# relay.net
KiCad netlist of a schematic drawn in Altium Designer
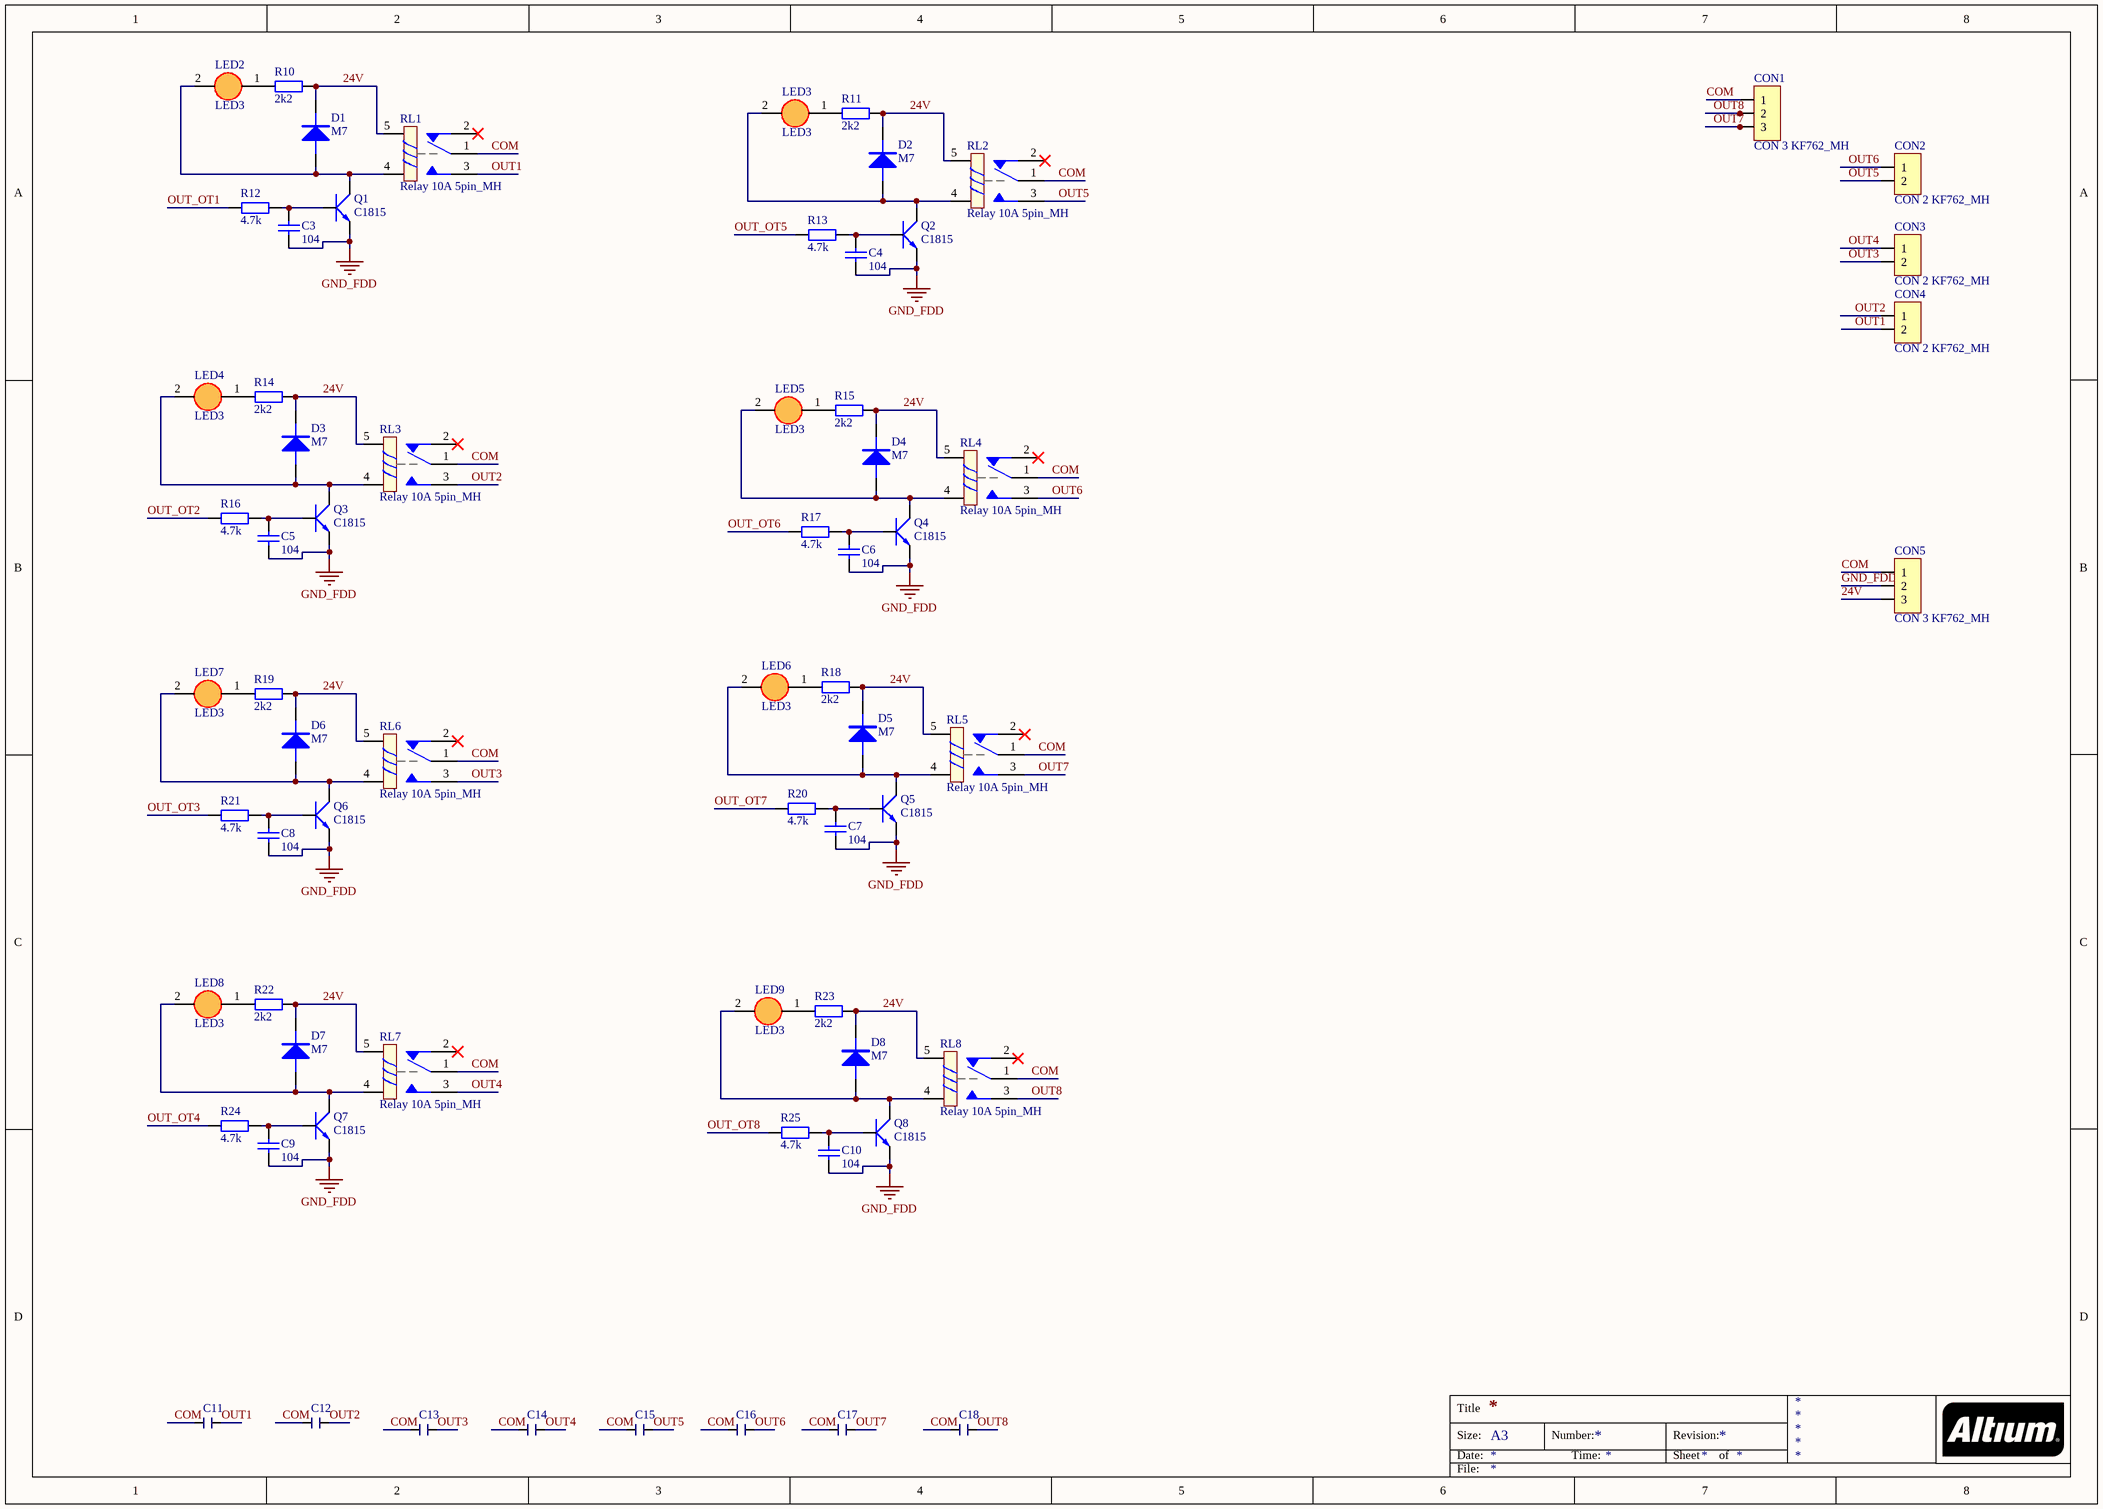
[diagram p0: relay.SchDoc]

(export (version "E")
  (design (tool "Eeschema 10.0.6"))
  (components
    (comp (ref "C3")
      (value "104")
      (footprint "TU_SMD_0805")
      (libsource (lib "MH_DA_THU_VIEN_ALTIUM_19112016") (part "TU_SMD_0805_MH"))
    )
    (comp (ref "C4")
      (value "104")
      (footprint "TU_SMD_0805")
      (libsource (lib "MH_DA_THU_VIEN_ALTIUM_19112016") (part "TU_SMD_0805_MH"))
    )
    (comp (ref "C5")
      (value "104")
      (footprint "TU_SMD_0805")
      (libsource (lib "MH_DA_THU_VIEN_ALTIUM_19112016") (part "TU_SMD_0805_MH"))
    )
    (comp (ref "C6")
      (value "104")
      (footprint "TU_SMD_0805")
      (libsource (lib "MH_DA_THU_VIEN_ALTIUM_19112016") (part "TU_SMD_0805_MH"))
    )
    (comp (ref "C7")
      (value "104")
      (footprint "TU_SMD_0805")
      (libsource (lib "MH_DA_THU_VIEN_ALTIUM_19112016") (part "TU_SMD_0805_MH"))
    )
    (comp (ref "C8")
      (value "104")
      (footprint "TU_SMD_0805")
      (libsource (lib "MH_DA_THU_VIEN_ALTIUM_19112016") (part "TU_SMD_0805_MH"))
    )
    (comp (ref "C9")
      (value "104")
      (footprint "TU_SMD_0805")
      (libsource (lib "MH_DA_THU_VIEN_ALTIUM_19112016") (part "TU_SMD_0805_MH"))
    )
    (comp (ref "C10")
      (value "104")
      (footprint "TU_SMD_0805")
      (libsource (lib "MH_DA_THU_VIEN_ALTIUM_19112016") (part "TU_SMD_0805_MH"))
    )
    (comp (ref "C11")
      (value "TU_CAO__AP_103_102_101_1KV_MH")
      (footprint "TU_TATA_5.08")
      (description "103 1KV")
      (libsource (lib "MH_DA_THU_VIEN_ALTIUM_19112016") (part "TU_CAO__AP_103_102_101_1KV_MH"))
    )
    (comp (ref "C12")
      (value "TU_CAO__AP_103_102_101_1KV_MH")
      (footprint "TU_TATA_5.08")
      (description "103 1KV")
      (libsource (lib "MH_DA_THU_VIEN_ALTIUM_19112016") (part "TU_CAO__AP_103_102_101_1KV_MH"))
    )
    (comp (ref "C13")
      (value "TU_CAO__AP_103_102_101_1KV_MH")
      (footprint "TU_TATA_5.08")
      (description "103 1KV")
      (libsource (lib "MH_DA_THU_VIEN_ALTIUM_19112016") (part "TU_CAO__AP_103_102_101_1KV_MH"))
    )
    (comp (ref "C14")
      (value "TU_CAO__AP_103_102_101_1KV_MH")
      (footprint "TU_TATA_5.08")
      (description "103 1KV")
      (libsource (lib "MH_DA_THU_VIEN_ALTIUM_19112016") (part "TU_CAO__AP_103_102_101_1KV_MH"))
    )
    (comp (ref "C15")
      (value "TU_CAO__AP_103_102_101_1KV_MH")
      (footprint "TU_TATA_5.08")
      (description "103 1KV")
      (libsource (lib "MH_DA_THU_VIEN_ALTIUM_19112016") (part "TU_CAO__AP_103_102_101_1KV_MH"))
    )
    (comp (ref "C16")
      (value "TU_CAO__AP_103_102_101_1KV_MH")
      (footprint "TU_TATA_5.08")
      (description "103 1KV")
      (libsource (lib "MH_DA_THU_VIEN_ALTIUM_19112016") (part "TU_CAO__AP_103_102_101_1KV_MH"))
    )
    (comp (ref "C17")
      (value "TU_CAO__AP_103_102_101_1KV_MH")
      (footprint "TU_TATA_5.08")
      (description "103 1KV")
      (libsource (lib "MH_DA_THU_VIEN_ALTIUM_19112016") (part "TU_CAO__AP_103_102_101_1KV_MH"))
    )
    (comp (ref "C18")
      (value "TU_CAO__AP_103_102_101_1KV_MH")
      (footprint "TU_TATA_5.08")
      (description "103 1KV")
      (libsource (lib "MH_DA_THU_VIEN_ALTIUM_19112016") (part "TU_CAO__AP_103_102_101_1KV_MH"))
    )
    (comp (ref "CON1")
      (value "CON 3 KF762_MH")
      (footprint "Con 3 KF762")
      (description "CON 3 KF762 - 3P 7.62mm")
      (libsource (lib "MH_DA_THU_VIEN_ALTIUM_19112016") (part "CON 3 KF762_MH"))
    )
    (comp (ref "CON2")
      (value "CON 2 KF762_MH")
      (footprint "Con 2 KF762")
      (description "CON 2 KF762 - 2P 7.62mm")
      (libsource (lib "MH_DA_THU_VIEN_ALTIUM_19112016") (part "CON 2 KF762_MH"))
    )
    (comp (ref "CON3")
      (value "CON 2 KF762_MH")
      (footprint "Con 2 KF762")
      (description "CON 2 KF762 - 2P 7.62mm")
      (libsource (lib "MH_DA_THU_VIEN_ALTIUM_19112016") (part "CON 2 KF762_MH"))
    )
    (comp (ref "CON4")
      (value "CON 2 KF762_MH")
      (footprint "Con 2 KF762")
      (description "CON 2 KF762 - 2P 7.62mm")
      (libsource (lib "MH_DA_THU_VIEN_ALTIUM_19112016") (part "CON 2 KF762_MH"))
    )
    (comp (ref "CON5")
      (value "CON 3 KF762_MH")
      (footprint "Con 3 KF762")
      (description "CON 3 KF762 - 3P 7.62mm")
      (libsource (lib "MH_DA_THU_VIEN_ALTIUM_19112016") (part "CON 3 KF762_MH"))
    )
    (comp (ref "D1")
      (value "M7")
      (footprint "SOD80")
      (description "Diode 1N4148 SOD80 450mA 100V ( LL34 1N4148 SMD)")
      (libsource (lib "MH_DA_THU_VIEN_ALTIUM_19112016") (part "Diode 1N4148 SOD80 450mA 100V ( LL34 1N4148 SMD)_MH"))
    )
    (comp (ref "D2")
      (value "M7")
      (footprint "SOD80")
      (description "Diode 1N4148 SOD80 450mA 100V ( LL34 1N4148 SMD)")
      (libsource (lib "MH_DA_THU_VIEN_ALTIUM_19112016") (part "Diode 1N4148 SOD80 450mA 100V ( LL34 1N4148 SMD)_MH"))
    )
    (comp (ref "D3")
      (value "M7")
      (footprint "SOD80")
      (description "Diode 1N4148 SOD80 450mA 100V ( LL34 1N4148 SMD)")
      (libsource (lib "MH_DA_THU_VIEN_ALTIUM_19112016") (part "Diode 1N4148 SOD80 450mA 100V ( LL34 1N4148 SMD)_MH"))
    )
    (comp (ref "D4")
      (value "M7")
      (footprint "SOD80")
      (description "Diode 1N4148 SOD80 450mA 100V ( LL34 1N4148 SMD)")
      (libsource (lib "MH_DA_THU_VIEN_ALTIUM_19112016") (part "Diode 1N4148 SOD80 450mA 100V ( LL34 1N4148 SMD)_MH"))
    )
    (comp (ref "D5")
      (value "M7")
      (footprint "SOD80")
      (description "Diode 1N4148 SOD80 450mA 100V ( LL34 1N4148 SMD)")
      (libsource (lib "MH_DA_THU_VIEN_ALTIUM_19112016") (part "Diode 1N4148 SOD80 450mA 100V ( LL34 1N4148 SMD)_MH"))
    )
    (comp (ref "D6")
      (value "M7")
      (footprint "SOD80")
      (description "Diode 1N4148 SOD80 450mA 100V ( LL34 1N4148 SMD)")
      (libsource (lib "MH_DA_THU_VIEN_ALTIUM_19112016") (part "Diode 1N4148 SOD80 450mA 100V ( LL34 1N4148 SMD)_MH"))
    )
    (comp (ref "D7")
      (value "M7")
      (footprint "SOD80")
      (description "Diode 1N4148 SOD80 450mA 100V ( LL34 1N4148 SMD)")
      (libsource (lib "MH_DA_THU_VIEN_ALTIUM_19112016") (part "Diode 1N4148 SOD80 450mA 100V ( LL34 1N4148 SMD)_MH"))
    )
    (comp (ref "D8")
      (value "M7")
      (footprint "SOD80")
      (description "Diode 1N4148 SOD80 450mA 100V ( LL34 1N4148 SMD)")
      (libsource (lib "MH_DA_THU_VIEN_ALTIUM_19112016") (part "Diode 1N4148 SOD80 450mA 100V ( LL34 1N4148 SMD)_MH"))
    )
    (comp (ref "LED2")
      (value "LED3")
      (footprint "LED 3mm Do")
      (description "LED 3mm")
      (libsource (lib "MH_DA_THU_VIEN_ALTIUM_19112016") (part "LED 3mm_MH"))
    )
    (comp (ref "LED3")
      (value "LED3")
      (footprint "LED 3mm Do")
      (description "LED 3mm")
      (libsource (lib "MH_DA_THU_VIEN_ALTIUM_19112016") (part "LED 3mm_MH"))
    )
    (comp (ref "LED4")
      (value "LED3")
      (footprint "LED 3mm Do")
      (description "LED 3mm")
      (libsource (lib "MH_DA_THU_VIEN_ALTIUM_19112016") (part "LED 3mm_MH"))
    )
    (comp (ref "LED5")
      (value "LED3")
      (footprint "LED 3mm Do")
      (description "LED 3mm")
      (libsource (lib "MH_DA_THU_VIEN_ALTIUM_19112016") (part "LED 3mm_MH"))
    )
    (comp (ref "LED6")
      (value "LED3")
      (footprint "LED 3mm Do")
      (description "LED 3mm")
      (libsource (lib "MH_DA_THU_VIEN_ALTIUM_19112016") (part "LED 3mm_MH"))
    )
    (comp (ref "LED7")
      (value "LED3")
      (footprint "LED 3mm Do")
      (description "LED 3mm")
      (libsource (lib "MH_DA_THU_VIEN_ALTIUM_19112016") (part "LED 3mm_MH"))
    )
    (comp (ref "LED8")
      (value "LED3")
      (footprint "LED 3mm Do")
      (description "LED 3mm")
      (libsource (lib "MH_DA_THU_VIEN_ALTIUM_19112016") (part "LED 3mm_MH"))
    )
    (comp (ref "LED9")
      (value "LED3")
      (footprint "LED 3mm Do")
      (description "LED 3mm")
      (libsource (lib "MH_DA_THU_VIEN_ALTIUM_19112016") (part "LED 3mm_MH"))
    )
    (comp (ref "Q1")
      (value "C1815")
      (footprint "SOT23")
      (libsource (lib "MH_DA_THU_VIEN_ALTIUM_19112016") (part "C1815 SOT23 TRANS NPN 0.15A 50V (SMD-HF)_MH"))
    )
    (comp (ref "Q2")
      (value "C1815")
      (footprint "SOT23")
      (libsource (lib "MH_DA_THU_VIEN_ALTIUM_19112016") (part "C1815 SOT23 TRANS NPN 0.15A 50V (SMD-HF)_MH"))
    )
    (comp (ref "Q3")
      (value "C1815")
      (footprint "SOT23")
      (libsource (lib "MH_DA_THU_VIEN_ALTIUM_19112016") (part "C1815 SOT23 TRANS NPN 0.15A 50V (SMD-HF)_MH"))
    )
    (comp (ref "Q4")
      (value "C1815")
      (footprint "SOT23")
      (libsource (lib "MH_DA_THU_VIEN_ALTIUM_19112016") (part "C1815 SOT23 TRANS NPN 0.15A 50V (SMD-HF)_MH"))
    )
    (comp (ref "Q5")
      (value "C1815")
      (footprint "SOT23")
      (libsource (lib "MH_DA_THU_VIEN_ALTIUM_19112016") (part "C1815 SOT23 TRANS NPN 0.15A 50V (SMD-HF)_MH"))
    )
    (comp (ref "Q6")
      (value "C1815")
      (footprint "SOT23")
      (libsource (lib "MH_DA_THU_VIEN_ALTIUM_19112016") (part "C1815 SOT23 TRANS NPN 0.15A 50V (SMD-HF)_MH"))
    )
    (comp (ref "Q7")
      (value "C1815")
      (footprint "SOT23")
      (libsource (lib "MH_DA_THU_VIEN_ALTIUM_19112016") (part "C1815 SOT23 TRANS NPN 0.15A 50V (SMD-HF)_MH"))
    )
    (comp (ref "Q8")
      (value "C1815")
      (footprint "SOT23")
      (libsource (lib "MH_DA_THU_VIEN_ALTIUM_19112016") (part "C1815 SOT23 TRANS NPN 0.15A 50V (SMD-HF)_MH"))
    )
    (comp (ref "R10")
      (value "2k2")
      (footprint "Tro SMD 0805")
      (description "TRO_SMD_0805")
      (libsource (lib "MH_DA_THU_VIEN_ALTIUM_19112016") (part "TRO_SMD_0805_MH"))
    )
    (comp (ref "R11")
      (value "2k2")
      (footprint "Tro SMD 0805")
      (description "TRO_SMD_0805")
      (libsource (lib "MH_DA_THU_VIEN_ALTIUM_19112016") (part "TRO_SMD_0805_MH"))
    )
    (comp (ref "R12")
      (value "4.7k")
      (footprint "Tro SMD 0805")
      (description "TRO_SMD_0805")
      (libsource (lib "MH_DA_THU_VIEN_ALTIUM_19112016") (part "TRO_SMD_0805_MH"))
    )
    (comp (ref "R13")
      (value "4.7k")
      (footprint "Tro SMD 0805")
      (description "TRO_SMD_0805")
      (libsource (lib "MH_DA_THU_VIEN_ALTIUM_19112016") (part "TRO_SMD_0805_MH"))
    )
    (comp (ref "R14")
      (value "2k2")
      (footprint "Tro SMD 0805")
      (description "TRO_SMD_0805")
      (libsource (lib "MH_DA_THU_VIEN_ALTIUM_19112016") (part "TRO_SMD_0805_MH"))
    )
    (comp (ref "R15")
      (value "2k2")
      (footprint "Tro SMD 0805")
      (description "TRO_SMD_0805")
      (libsource (lib "MH_DA_THU_VIEN_ALTIUM_19112016") (part "TRO_SMD_0805_MH"))
    )
    (comp (ref "R16")
      (value "4.7k")
      (footprint "Tro SMD 0805")
      (description "TRO_SMD_0805")
      (libsource (lib "MH_DA_THU_VIEN_ALTIUM_19112016") (part "TRO_SMD_0805_MH"))
    )
    (comp (ref "R17")
      (value "4.7k")
      (footprint "Tro SMD 0805")
      (description "TRO_SMD_0805")
      (libsource (lib "MH_DA_THU_VIEN_ALTIUM_19112016") (part "TRO_SMD_0805_MH"))
    )
    (comp (ref "R18")
      (value "2k2")
      (footprint "Tro SMD 0805")
      (description "TRO_SMD_0805")
      (libsource (lib "MH_DA_THU_VIEN_ALTIUM_19112016") (part "TRO_SMD_0805_MH"))
    )
    (comp (ref "R19")
      (value "2k2")
      (footprint "Tro SMD 0805")
      (description "TRO_SMD_0805")
      (libsource (lib "MH_DA_THU_VIEN_ALTIUM_19112016") (part "TRO_SMD_0805_MH"))
    )
    (comp (ref "R20")
      (value "4.7k")
      (footprint "Tro SMD 0805")
      (description "TRO_SMD_0805")
      (libsource (lib "MH_DA_THU_VIEN_ALTIUM_19112016") (part "TRO_SMD_0805_MH"))
    )
    (comp (ref "R21")
      (value "4.7k")
      (footprint "Tro SMD 0805")
      (description "TRO_SMD_0805")
      (libsource (lib "MH_DA_THU_VIEN_ALTIUM_19112016") (part "TRO_SMD_0805_MH"))
    )
    (comp (ref "R22")
      (value "2k2")
      (footprint "Tro SMD 0805")
      (description "TRO_SMD_0805")
      (libsource (lib "MH_DA_THU_VIEN_ALTIUM_19112016") (part "TRO_SMD_0805_MH"))
    )
    (comp (ref "R23")
      (value "2k2")
      (footprint "Tro SMD 0805")
      (description "TRO_SMD_0805")
      (libsource (lib "MH_DA_THU_VIEN_ALTIUM_19112016") (part "TRO_SMD_0805_MH"))
    )
    (comp (ref "R24")
      (value "4.7k")
      (footprint "Tro SMD 0805")
      (description "TRO_SMD_0805")
      (libsource (lib "MH_DA_THU_VIEN_ALTIUM_19112016") (part "TRO_SMD_0805_MH"))
    )
    (comp (ref "R25")
      (value "4.7k")
      (footprint "Tro SMD 0805")
      (description "TRO_SMD_0805")
      (libsource (lib "MH_DA_THU_VIEN_ALTIUM_19112016") (part "TRO_SMD_0805_MH"))
    )
    (comp (ref "RL1")
      (value "Relay 10A 5pin_MH")
      (footprint "relay 10A 5pin")
      (description "Relay")
      (libsource (lib "MH_DA_THU_VIEN_ALTIUM_19112016") (part "Relay 10A 5pin_MH"))
    )
    (comp (ref "RL2")
      (value "Relay 10A 5pin_MH")
      (footprint "relay 10A 5pin")
      (description "Relay")
      (libsource (lib "MH_DA_THU_VIEN_ALTIUM_19112016") (part "Relay 10A 5pin_MH"))
    )
    (comp (ref "RL3")
      (value "Relay 10A 5pin_MH")
      (footprint "relay 10A 5pin")
      (description "Relay")
      (libsource (lib "MH_DA_THU_VIEN_ALTIUM_19112016") (part "Relay 10A 5pin_MH"))
    )
    (comp (ref "RL4")
      (value "Relay 10A 5pin_MH")
      (footprint "relay 10A 5pin")
      (description "Relay")
      (libsource (lib "MH_DA_THU_VIEN_ALTIUM_19112016") (part "Relay 10A 5pin_MH"))
    )
    (comp (ref "RL5")
      (value "Relay 10A 5pin_MH")
      (footprint "relay 10A 5pin")
      (description "Relay")
      (libsource (lib "MH_DA_THU_VIEN_ALTIUM_19112016") (part "Relay 10A 5pin_MH"))
    )
    (comp (ref "RL6")
      (value "Relay 10A 5pin_MH")
      (footprint "relay 10A 5pin")
      (description "Relay")
      (libsource (lib "MH_DA_THU_VIEN_ALTIUM_19112016") (part "Relay 10A 5pin_MH"))
    )
    (comp (ref "RL7")
      (value "Relay 10A 5pin_MH")
      (footprint "relay 10A 5pin")
      (description "Relay")
      (libsource (lib "MH_DA_THU_VIEN_ALTIUM_19112016") (part "Relay 10A 5pin_MH"))
    )
    (comp (ref "RL8")
      (value "Relay 10A 5pin_MH")
      (footprint "relay 10A 5pin")
      (description "Relay")
      (libsource (lib "MH_DA_THU_VIEN_ALTIUM_19112016") (part "Relay 10A 5pin_MH"))
    )
  )
  (nets
    (net (code "1") (name "/24V") (class "Default")
      (node (ref "CON5") (pin "3") (pinfunction "3_3") (pintype "passive"))
      (node (ref "D1") (pin "2") (pinfunction "2_2") (pintype "passive"))
      (node (ref "D2") (pin "2") (pinfunction "2_2") (pintype "passive"))
      (node (ref "D3") (pin "2") (pinfunction "2_2") (pintype "passive"))
      (node (ref "D4") (pin "2") (pinfunction "2_2") (pintype "passive"))
      (node (ref "D5") (pin "2") (pinfunction "2_2") (pintype "passive"))
      (node (ref "D6") (pin "2") (pinfunction "2_2") (pintype "passive"))
      (node (ref "D7") (pin "2") (pinfunction "2_2") (pintype "passive"))
      (node (ref "D8") (pin "2") (pinfunction "2_2") (pintype "passive"))
      (node (ref "R10") (pin "2") (pinfunction "2_2") (pintype "passive"))
      (node (ref "R11") (pin "2") (pinfunction "2_2") (pintype "passive"))
      (node (ref "R14") (pin "2") (pinfunction "2_2") (pintype "passive"))
      (node (ref "R15") (pin "2") (pinfunction "2_2") (pintype "passive"))
      (node (ref "R18") (pin "2") (pinfunction "2_2") (pintype "passive"))
      (node (ref "R19") (pin "2") (pinfunction "2_2") (pintype "passive"))
      (node (ref "R22") (pin "2") (pinfunction "2_2") (pintype "passive"))
      (node (ref "R23") (pin "2") (pinfunction "2_2") (pintype "passive"))
      (node (ref "RL1") (pin "5") (pinfunction "5_5") (pintype "passive"))
      (node (ref "RL2") (pin "5") (pinfunction "5_5") (pintype "passive"))
      (node (ref "RL3") (pin "5") (pinfunction "5_5") (pintype "passive"))
      (node (ref "RL4") (pin "5") (pinfunction "5_5") (pintype "passive"))
      (node (ref "RL5") (pin "5") (pinfunction "5_5") (pintype "passive"))
      (node (ref "RL6") (pin "5") (pinfunction "5_5") (pintype "passive"))
      (node (ref "RL7") (pin "5") (pinfunction "5_5") (pintype "passive"))
      (node (ref "RL8") (pin "5") (pinfunction "5_5") (pintype "passive"))
    )
    (net (code "2") (name "/COM") (class "Default")
      (node (ref "C11") (pin "1") (pinfunction "1_1") (pintype "passive"))
      (node (ref "C12") (pin "1") (pinfunction "1_1") (pintype "passive"))
      (node (ref "C13") (pin "1") (pinfunction "1_1") (pintype "passive"))
      (node (ref "C14") (pin "1") (pinfunction "1_1") (pintype "passive"))
      (node (ref "C15") (pin "1") (pinfunction "1_1") (pintype "passive"))
      (node (ref "C16") (pin "1") (pinfunction "1_1") (pintype "passive"))
      (node (ref "C17") (pin "1") (pinfunction "1_1") (pintype "passive"))
      (node (ref "C18") (pin "1") (pinfunction "1_1") (pintype "passive"))
      (node (ref "CON1") (pin "1") (pinfunction "1_1") (pintype "passive"))
      (node (ref "CON5") (pin "1") (pinfunction "1_1") (pintype "passive"))
      (node (ref "RL1") (pin "1") (pinfunction "1_1") (pintype "passive"))
      (node (ref "RL2") (pin "1") (pinfunction "1_1") (pintype "passive"))
      (node (ref "RL3") (pin "1") (pinfunction "1_1") (pintype "passive"))
      (node (ref "RL4") (pin "1") (pinfunction "1_1") (pintype "passive"))
      (node (ref "RL5") (pin "1") (pinfunction "1_1") (pintype "passive"))
      (node (ref "RL6") (pin "1") (pinfunction "1_1") (pintype "passive"))
      (node (ref "RL7") (pin "1") (pinfunction "1_1") (pintype "passive"))
      (node (ref "RL8") (pin "1") (pinfunction "1_1") (pintype "passive"))
    )
    (net (code "3") (name "/OUT1") (class "Default")
      (node (ref "C11") (pin "2") (pinfunction "2_2") (pintype "passive"))
      (node (ref "CON4") (pin "2") (pinfunction "2_2") (pintype "passive"))
      (node (ref "RL1") (pin "3") (pinfunction "3_3") (pintype "passive"))
    )
    (net (code "4") (name "/OUT2") (class "Default")
      (node (ref "C12") (pin "2") (pinfunction "2_2") (pintype "passive"))
      (node (ref "CON4") (pin "1") (pinfunction "1_1") (pintype "passive"))
      (node (ref "RL3") (pin "3") (pinfunction "3_3") (pintype "passive"))
    )
    (net (code "5") (name "/OUT3") (class "Default")
      (node (ref "C13") (pin "2") (pinfunction "2_2") (pintype "passive"))
      (node (ref "CON3") (pin "2") (pinfunction "2_2") (pintype "passive"))
      (node (ref "RL6") (pin "3") (pinfunction "3_3") (pintype "passive"))
    )
    (net (code "6") (name "/OUT4") (class "Default")
      (node (ref "C14") (pin "2") (pinfunction "2_2") (pintype "passive"))
      (node (ref "CON3") (pin "1") (pinfunction "1_1") (pintype "passive"))
      (node (ref "RL7") (pin "3") (pinfunction "3_3") (pintype "passive"))
    )
    (net (code "7") (name "/OUT5") (class "Default")
      (node (ref "C15") (pin "2") (pinfunction "2_2") (pintype "passive"))
      (node (ref "CON2") (pin "2") (pinfunction "2_2") (pintype "passive"))
      (node (ref "RL2") (pin "3") (pinfunction "3_3") (pintype "passive"))
    )
    (net (code "8") (name "/OUT6") (class "Default")
      (node (ref "C16") (pin "2") (pinfunction "2_2") (pintype "passive"))
      (node (ref "CON2") (pin "1") (pinfunction "1_1") (pintype "passive"))
      (node (ref "RL4") (pin "3") (pinfunction "3_3") (pintype "passive"))
    )
    (net (code "9") (name "/OUT7") (class "Default")
      (node (ref "C17") (pin "2") (pinfunction "2_2") (pintype "passive"))
      (node (ref "CON1") (pin "3") (pinfunction "3_3") (pintype "passive"))
      (node (ref "RL5") (pin "3") (pinfunction "3_3") (pintype "passive"))
    )
    (net (code "10") (name "/OUT8") (class "Default")
      (node (ref "C18") (pin "2") (pinfunction "2_2") (pintype "passive"))
      (node (ref "CON1") (pin "2") (pinfunction "2_2") (pintype "passive"))
      (node (ref "RL8") (pin "3") (pinfunction "3_3") (pintype "passive"))
    )
    (net (code "11") (name "/OUT_OT1") (class "Default")
      (node (ref "R12") (pin "1") (pinfunction "1_1") (pintype "passive"))
    )
    (net (code "12") (name "/OUT_OT2") (class "Default")
      (node (ref "R16") (pin "1") (pinfunction "1_1") (pintype "passive"))
    )
    (net (code "13") (name "/OUT_OT3") (class "Default")
      (node (ref "R21") (pin "1") (pinfunction "1_1") (pintype "passive"))
    )
    (net (code "14") (name "/OUT_OT4") (class "Default")
      (node (ref "R24") (pin "1") (pinfunction "1_1") (pintype "passive"))
    )
    (net (code "15") (name "/OUT_OT5") (class "Default")
      (node (ref "R13") (pin "1") (pinfunction "1_1") (pintype "passive"))
    )
    (net (code "16") (name "/OUT_OT6") (class "Default")
      (node (ref "R17") (pin "1") (pinfunction "1_1") (pintype "passive"))
    )
    (net (code "17") (name "/OUT_OT7") (class "Default")
      (node (ref "R20") (pin "1") (pinfunction "1_1") (pintype "passive"))
    )
    (net (code "18") (name "/OUT_OT8") (class "Default")
      (node (ref "R25") (pin "1") (pinfunction "1_1") (pintype "passive"))
    )
    (net (code "19") (name "GND_FDD") (class "Default")
      (node (ref "C10") (pin "1") (pinfunction "1_1") (pintype "passive"))
      (node (ref "C3") (pin "1") (pinfunction "1_1") (pintype "passive"))
      (node (ref "C4") (pin "1") (pinfunction "1_1") (pintype "passive"))
      (node (ref "C5") (pin "1") (pinfunction "1_1") (pintype "passive"))
      (node (ref "C6") (pin "1") (pinfunction "1_1") (pintype "passive"))
      (node (ref "C7") (pin "1") (pinfunction "1_1") (pintype "passive"))
      (node (ref "C8") (pin "1") (pinfunction "1_1") (pintype "passive"))
      (node (ref "C9") (pin "1") (pinfunction "1_1") (pintype "passive"))
      (node (ref "CON5") (pin "2") (pinfunction "2_2") (pintype "passive"))
      (node (ref "Q1") (pin "2") (pinfunction "E_2") (pintype "passive"))
      (node (ref "Q2") (pin "2") (pinfunction "E_2") (pintype "passive"))
      (node (ref "Q3") (pin "2") (pinfunction "E_2") (pintype "passive"))
      (node (ref "Q4") (pin "2") (pinfunction "E_2") (pintype "passive"))
      (node (ref "Q5") (pin "2") (pinfunction "E_2") (pintype "passive"))
      (node (ref "Q6") (pin "2") (pinfunction "E_2") (pintype "passive"))
      (node (ref "Q7") (pin "2") (pinfunction "E_2") (pintype "passive"))
      (node (ref "Q8") (pin "2") (pinfunction "E_2") (pintype "passive"))
    )
    (net (code "20") (name "Net-(LED2-A)") (class "Default")
      (node (ref "LED2") (pin "1") (pinfunction "A_1") (pintype "passive"))
      (node (ref "R10") (pin "1") (pinfunction "1_1") (pintype "passive"))
    )
    (net (code "21") (name "Net-(LED2-K)") (class "Default")
      (node (ref "D1") (pin "1") (pinfunction "1_1") (pintype "passive"))
      (node (ref "LED2") (pin "2") (pinfunction "K_2") (pintype "passive"))
      (node (ref "Q1") (pin "3") (pinfunction "C_3") (pintype "passive"))
      (node (ref "RL1") (pin "4") (pinfunction "4_4") (pintype "passive"))
    )
    (net (code "22") (name "Net-(LED3-A)") (class "Default")
      (node (ref "LED3") (pin "1") (pinfunction "A_1") (pintype "passive"))
      (node (ref "R11") (pin "1") (pinfunction "1_1") (pintype "passive"))
    )
    (net (code "23") (name "Net-(LED3-K)") (class "Default")
      (node (ref "D2") (pin "1") (pinfunction "1_1") (pintype "passive"))
      (node (ref "LED3") (pin "2") (pinfunction "K_2") (pintype "passive"))
      (node (ref "Q2") (pin "3") (pinfunction "C_3") (pintype "passive"))
      (node (ref "RL2") (pin "4") (pinfunction "4_4") (pintype "passive"))
    )
    (net (code "24") (name "Net-(LED4-A)") (class "Default")
      (node (ref "LED4") (pin "1") (pinfunction "A_1") (pintype "passive"))
      (node (ref "R14") (pin "1") (pinfunction "1_1") (pintype "passive"))
    )
    (net (code "25") (name "Net-(LED4-K)") (class "Default")
      (node (ref "D3") (pin "1") (pinfunction "1_1") (pintype "passive"))
      (node (ref "LED4") (pin "2") (pinfunction "K_2") (pintype "passive"))
      (node (ref "Q3") (pin "3") (pinfunction "C_3") (pintype "passive"))
      (node (ref "RL3") (pin "4") (pinfunction "4_4") (pintype "passive"))
    )
    (net (code "26") (name "Net-(LED5-A)") (class "Default")
      (node (ref "LED5") (pin "1") (pinfunction "A_1") (pintype "passive"))
      (node (ref "R15") (pin "1") (pinfunction "1_1") (pintype "passive"))
    )
    (net (code "27") (name "Net-(LED5-K)") (class "Default")
      (node (ref "D4") (pin "1") (pinfunction "1_1") (pintype "passive"))
      (node (ref "LED5") (pin "2") (pinfunction "K_2") (pintype "passive"))
      (node (ref "Q4") (pin "3") (pinfunction "C_3") (pintype "passive"))
      (node (ref "RL4") (pin "4") (pinfunction "4_4") (pintype "passive"))
    )
    (net (code "28") (name "Net-(LED6-A)") (class "Default")
      (node (ref "LED6") (pin "1") (pinfunction "A_1") (pintype "passive"))
      (node (ref "R18") (pin "1") (pinfunction "1_1") (pintype "passive"))
    )
    (net (code "29") (name "Net-(LED6-K)") (class "Default")
      (node (ref "D5") (pin "1") (pinfunction "1_1") (pintype "passive"))
      (node (ref "LED6") (pin "2") (pinfunction "K_2") (pintype "passive"))
      (node (ref "Q5") (pin "3") (pinfunction "C_3") (pintype "passive"))
      (node (ref "RL5") (pin "4") (pinfunction "4_4") (pintype "passive"))
    )
    (net (code "30") (name "Net-(LED7-A)") (class "Default")
      (node (ref "LED7") (pin "1") (pinfunction "A_1") (pintype "passive"))
      (node (ref "R19") (pin "1") (pinfunction "1_1") (pintype "passive"))
    )
    (net (code "31") (name "Net-(LED7-K)") (class "Default")
      (node (ref "D6") (pin "1") (pinfunction "1_1") (pintype "passive"))
      (node (ref "LED7") (pin "2") (pinfunction "K_2") (pintype "passive"))
      (node (ref "Q6") (pin "3") (pinfunction "C_3") (pintype "passive"))
      (node (ref "RL6") (pin "4") (pinfunction "4_4") (pintype "passive"))
    )
    (net (code "32") (name "Net-(LED8-A)") (class "Default")
      (node (ref "LED8") (pin "1") (pinfunction "A_1") (pintype "passive"))
      (node (ref "R22") (pin "1") (pinfunction "1_1") (pintype "passive"))
    )
    (net (code "33") (name "Net-(LED8-K)") (class "Default")
      (node (ref "D7") (pin "1") (pinfunction "1_1") (pintype "passive"))
      (node (ref "LED8") (pin "2") (pinfunction "K_2") (pintype "passive"))
      (node (ref "Q7") (pin "3") (pinfunction "C_3") (pintype "passive"))
      (node (ref "RL7") (pin "4") (pinfunction "4_4") (pintype "passive"))
    )
    (net (code "34") (name "Net-(LED9-A)") (class "Default")
      (node (ref "LED9") (pin "1") (pinfunction "A_1") (pintype "passive"))
      (node (ref "R23") (pin "1") (pinfunction "1_1") (pintype "passive"))
    )
    (net (code "35") (name "Net-(LED9-K)") (class "Default")
      (node (ref "D8") (pin "1") (pinfunction "1_1") (pintype "passive"))
      (node (ref "LED9") (pin "2") (pinfunction "K_2") (pintype "passive"))
      (node (ref "Q8") (pin "3") (pinfunction "C_3") (pintype "passive"))
      (node (ref "RL8") (pin "4") (pinfunction "4_4") (pintype "passive"))
    )
    (net (code "36") (name "Net-(Q1-B)") (class "Default")
      (node (ref "C3") (pin "2") (pinfunction "2_2") (pintype "passive"))
      (node (ref "Q1") (pin "1") (pinfunction "B_1") (pintype "passive"))
      (node (ref "R12") (pin "2") (pinfunction "2_2") (pintype "passive"))
    )
    (net (code "37") (name "Net-(Q2-B)") (class "Default")
      (node (ref "C4") (pin "2") (pinfunction "2_2") (pintype "passive"))
      (node (ref "Q2") (pin "1") (pinfunction "B_1") (pintype "passive"))
      (node (ref "R13") (pin "2") (pinfunction "2_2") (pintype "passive"))
    )
    (net (code "38") (name "Net-(Q3-B)") (class "Default")
      (node (ref "C5") (pin "2") (pinfunction "2_2") (pintype "passive"))
      (node (ref "Q3") (pin "1") (pinfunction "B_1") (pintype "passive"))
      (node (ref "R16") (pin "2") (pinfunction "2_2") (pintype "passive"))
    )
    (net (code "39") (name "Net-(Q4-B)") (class "Default")
      (node (ref "C6") (pin "2") (pinfunction "2_2") (pintype "passive"))
      (node (ref "Q4") (pin "1") (pinfunction "B_1") (pintype "passive"))
      (node (ref "R17") (pin "2") (pinfunction "2_2") (pintype "passive"))
    )
    (net (code "40") (name "Net-(Q5-B)") (class "Default")
      (node (ref "C7") (pin "2") (pinfunction "2_2") (pintype "passive"))
      (node (ref "Q5") (pin "1") (pinfunction "B_1") (pintype "passive"))
      (node (ref "R20") (pin "2") (pinfunction "2_2") (pintype "passive"))
    )
    (net (code "41") (name "Net-(Q6-B)") (class "Default")
      (node (ref "C8") (pin "2") (pinfunction "2_2") (pintype "passive"))
      (node (ref "Q6") (pin "1") (pinfunction "B_1") (pintype "passive"))
      (node (ref "R21") (pin "2") (pinfunction "2_2") (pintype "passive"))
    )
    (net (code "42") (name "Net-(Q7-B)") (class "Default")
      (node (ref "C9") (pin "2") (pinfunction "2_2") (pintype "passive"))
      (node (ref "Q7") (pin "1") (pinfunction "B_1") (pintype "passive"))
      (node (ref "R24") (pin "2") (pinfunction "2_2") (pintype "passive"))
    )
    (net (code "43") (name "Net-(Q8-B)") (class "Default")
      (node (ref "C10") (pin "2") (pinfunction "2_2") (pintype "passive"))
      (node (ref "Q8") (pin "1") (pinfunction "B_1") (pintype "passive"))
      (node (ref "R25") (pin "2") (pinfunction "2_2") (pintype "passive"))
    )
    (net (code "44") (name "unconnected-(RL1-Pad2)") (class "Default")
      (node (ref "RL1") (pin "2") (pinfunction "2_2") (pintype "passive+no_connect"))
    )
    (net (code "45") (name "unconnected-(RL2-Pad2)") (class "Default")
      (node (ref "RL2") (pin "2") (pinfunction "2_2") (pintype "passive+no_connect"))
    )
    (net (code "46") (name "unconnected-(RL3-Pad2)") (class "Default")
      (node (ref "RL3") (pin "2") (pinfunction "2_2") (pintype "passive+no_connect"))
    )
    (net (code "47") (name "unconnected-(RL4-Pad2)") (class "Default")
      (node (ref "RL4") (pin "2") (pinfunction "2_2") (pintype "passive+no_connect"))
    )
    (net (code "48") (name "unconnected-(RL5-Pad2)") (class "Default")
      (node (ref "RL5") (pin "2") (pinfunction "2_2") (pintype "passive+no_connect"))
    )
    (net (code "49") (name "unconnected-(RL6-Pad2)") (class "Default")
      (node (ref "RL6") (pin "2") (pinfunction "2_2") (pintype "passive+no_connect"))
    )
    (net (code "50") (name "unconnected-(RL7-Pad2)") (class "Default")
      (node (ref "RL7") (pin "2") (pinfunction "2_2") (pintype "passive+no_connect"))
    )
    (net (code "51") (name "unconnected-(RL8-Pad2)") (class "Default")
      (node (ref "RL8") (pin "2") (pinfunction "2_2") (pintype "passive+no_connect"))
    )
  )
)
